# PCB.net
KiCad netlist of a schematic drawn in Altium Designer
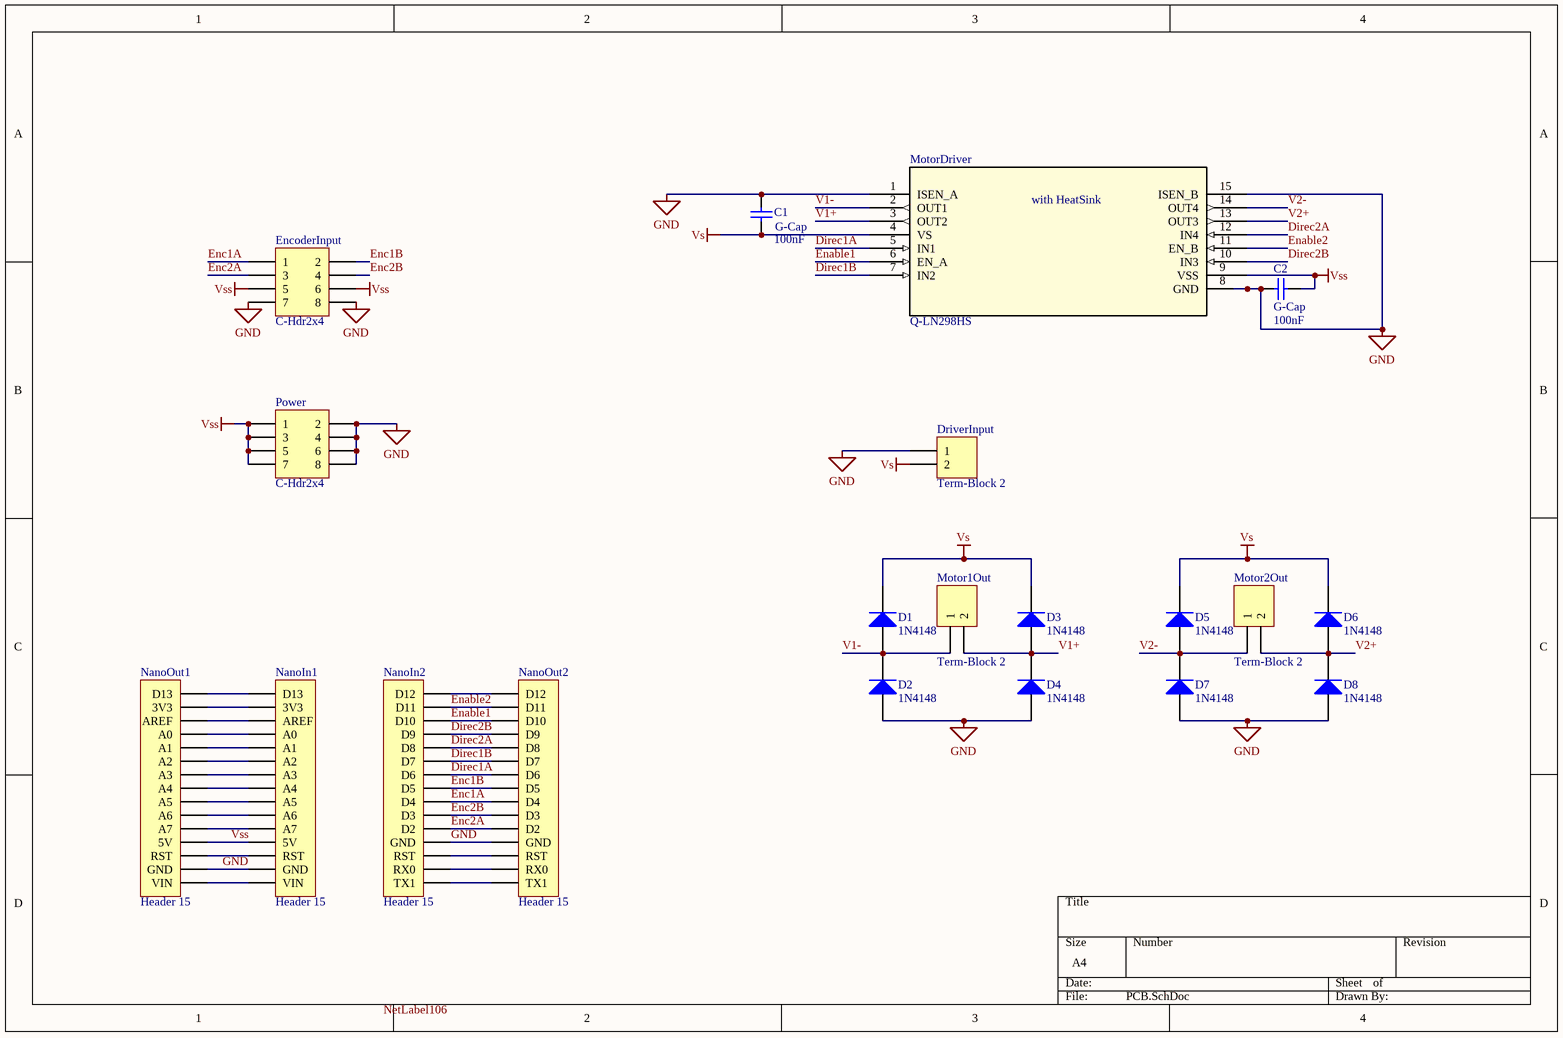
[diagram p0: PCB.SchDoc]

(export (version "E")
  (design (tool "Eeschema 10.0.6"))
  (components
    (comp (ref "C1")
      (value "G-Cap")
      (footprint "Cap2.54mm_LGE1.0")
      (description "Capacitor (specify value)")
      (fields (field (name "ALTIUM_VALUE") "100nF") (field (name "PUBLISHER") "Altium Limited"))
      (libsource (lib "PartsDatabaseV16.1") (part "G-Cap"))
    )
    (comp (ref "C2")
      (value "G-Cap")
      (footprint "Cap2.54mm_LGE1.0")
      (description "Capacitor (specify value)")
      (fields (field (name "ALTIUM_VALUE") "100nF") (field (name "PUBLISHER") "Altium Limited"))
      (libsource (lib "PartsDatabaseV16.1") (part "G-Cap"))
    )
    (comp (ref "D1")
      (value "1N4148")
      (footprint "DO-41_XLGE1.2")
      (description "High-speed Diode")
      (libsource (lib "PartsDatabaseV16.1") (part "T-DiodeRect"))
    )
    (comp (ref "D2")
      (value "1N4148")
      (footprint "DO-41_XLGE1.2")
      (description "High-speed Diode")
      (libsource (lib "PartsDatabaseV16.1") (part "T-DiodeRect"))
    )
    (comp (ref "D3")
      (value "1N4148")
      (footprint "DO-41_XLGE1.2")
      (description "High-speed Diode")
      (libsource (lib "PartsDatabaseV16.1") (part "T-DiodeRect"))
    )
    (comp (ref "D4")
      (value "1N4148")
      (footprint "DO-41_XLGE1.2")
      (description "High-speed Diode")
      (libsource (lib "PartsDatabaseV16.1") (part "T-DiodeRect"))
    )
    (comp (ref "D5")
      (value "1N4148")
      (footprint "DO-41_XLGE1.2")
      (description "High-speed Diode")
      (libsource (lib "PartsDatabaseV16.1") (part "T-DiodeRect"))
    )
    (comp (ref "D6")
      (value "1N4148")
      (footprint "DO-41_XLGE1.2")
      (description "High-speed Diode")
      (libsource (lib "PartsDatabaseV16.1") (part "T-DiodeRect"))
    )
    (comp (ref "D7")
      (value "1N4148")
      (footprint "DO-41_XLGE1.2")
      (description "High-speed Diode")
      (libsource (lib "PartsDatabaseV16.1") (part "T-DiodeRect"))
    )
    (comp (ref "D8")
      (value "1N4148")
      (footprint "DO-41_XLGE1.2")
      (description "High-speed Diode")
      (libsource (lib "PartsDatabaseV16.1") (part "T-DiodeRect"))
    )
    (comp (ref "DriverInput")
      (value "Term-Block 2")
      (footprint "TERM-BLOCK-5.08MM-2POS")
      (description "Terminal-Block 1x2")
      (fields (field (name "PUBLISHER") "Altium Limited"))
      (libsource (lib "PartsDatabaseV16.1") (part "C-Block2"))
    )
    (comp (ref "EncoderInput")
      (value "C-Hdr2x4")
      (footprint "HDR2X4_LGE1.0")
      (description "Header, 4-Pin, Dual row")
      (fields (field (name "PUBLISHER") "Altium Limited"))
      (libsource (lib "PartsDatabaseV16.1") (part "C-Hdr2x4"))
    )
    (comp (ref "Motor1Out")
      (value "Term-Block 2")
      (footprint "TERM-BLOCK-5.08MM-2POS")
      (description "Terminal-Block 1x2")
      (fields (field (name "PUBLISHER") "Altium Limited"))
      (libsource (lib "") (part "C-Block2_1"))
    )
    (comp (ref "Motor2Out")
      (value "Term-Block 2")
      (footprint "TERM-BLOCK-5.08MM-2POS")
      (description "Terminal-Block 1x2")
      (fields (field (name "PUBLISHER") "Altium Limited"))
      (libsource (lib "") (part "C-Block2_1"))
    )
    (comp (ref "MotorDriver")
      (value "Q-LN298HS")
      (footprint "Multiwatt15_V_ELEC391HS")
      (description "LN298 - IC Bridge Driver Par 15Multiwatt")
      (fields
        (field (name "MANUFACTURER_PART_NUMBER") "L298N")
        (field (name "COPYRIGHT") "Copyright (C) 2015 Accelerated Designs. All rights reserved")
      )
      (libsource (lib "Additional Parts 391") (part "Q-LN298HS"))
    )
    (comp (ref "NanoIn1")
      (value "Header 15")
      (footprint "HDR1X15")
      (description "Header, 15-Pin")
      (fields (field (name "PUBLISHER") "Altium Limited"))
      (libsource (lib "") (part "Header 15_2"))
    )
    (comp (ref "NanoIn2")
      (value "Header 15")
      (footprint "HDR1X15")
      (description "Header, 15-Pin")
      (fields (field (name "PUBLISHER") "Altium Limited"))
      (libsource (lib "Miscellaneous Connectors") (part "Header 15"))
    )
    (comp (ref "NanoOut1")
      (value "Header 15")
      (footprint "HDR1X15")
      (description "Header, 15-Pin")
      (fields (field (name "PUBLISHER") "Altium Limited"))
      (libsource (lib "Miscellaneous Connectors") (part "Header 15"))
    )
    (comp (ref "NanoOut2")
      (value "Header 15")
      (footprint "HDR1X15")
      (description "Header, 15-Pin")
      (fields (field (name "PUBLISHER") "Altium Limited"))
      (libsource (lib "") (part "Header 15_1"))
    )
    (comp (ref "Power")
      (value "C-Hdr2x4")
      (footprint "HDR2X4_LGE1.0")
      (description "Header, 4-Pin, Dual row")
      (fields (field (name "PUBLISHER") "Altium Limited"))
      (libsource (lib "PartsDatabaseV16.1") (part "C-Hdr2x4"))
    )
  )
  (nets
    (net (code "1") (name "/Direc1A") (class "Default")
      (node (ref "MotorDriver") (pin "5") (pinfunction "IN1_5") (pintype "input"))
      (node (ref "NanoIn2") (pin "7") (pinfunction "A3_7") (pintype "passive"))
      (node (ref "NanoOut2") (pin "7") (pinfunction "D6_7") (pintype "passive"))
    )
    (net (code "2") (name "/Direc1B") (class "Default")
      (node (ref "MotorDriver") (pin "7") (pinfunction "IN2_7") (pintype "input"))
      (node (ref "NanoIn2") (pin "6") (pinfunction "A2_6") (pintype "passive"))
      (node (ref "NanoOut2") (pin "6") (pinfunction "D7_6") (pintype "passive"))
    )
    (net (code "3") (name "/Direc2A") (class "Default")
      (node (ref "MotorDriver") (pin "12") (pinfunction "IN4_12") (pintype "input"))
      (node (ref "NanoIn2") (pin "5") (pinfunction "A1_5") (pintype "passive"))
      (node (ref "NanoOut2") (pin "5") (pinfunction "D8_5") (pintype "passive"))
    )
    (net (code "4") (name "/Direc2B") (class "Default")
      (node (ref "MotorDriver") (pin "10") (pinfunction "IN3_10") (pintype "input"))
      (node (ref "NanoIn2") (pin "4") (pinfunction "A0_4") (pintype "passive"))
      (node (ref "NanoOut2") (pin "4") (pinfunction "D9_4") (pintype "passive"))
    )
    (net (code "5") (name "/Enable1") (class "Default")
      (node (ref "MotorDriver") (pin "6") (pinfunction "EN_A_6") (pintype "input"))
      (node (ref "NanoIn2") (pin "3") (pinfunction "AREF_3") (pintype "passive"))
      (node (ref "NanoOut2") (pin "3") (pinfunction "D10_3") (pintype "passive"))
    )
    (net (code "6") (name "/Enable2") (class "Default")
      (node (ref "MotorDriver") (pin "11") (pinfunction "EN_B_11") (pintype "input"))
      (node (ref "NanoIn2") (pin "2") (pinfunction "3V3_2") (pintype "passive"))
      (node (ref "NanoOut2") (pin "2") (pinfunction "D11_2") (pintype "passive"))
    )
    (net (code "7") (name "/Enc1A") (class "Default")
      (node (ref "EncoderInput") (pin "1") (pinfunction "1_1") (pintype "passive"))
      (node (ref "NanoIn2") (pin "9") (pinfunction "A5_9") (pintype "passive"))
      (node (ref "NanoOut2") (pin "9") (pinfunction "D4_9") (pintype "passive"))
    )
    (net (code "8") (name "/Enc1B") (class "Default")
      (node (ref "EncoderInput") (pin "2") (pinfunction "2_2") (pintype "passive"))
      (node (ref "NanoIn2") (pin "8") (pinfunction "A4_8") (pintype "passive"))
      (node (ref "NanoOut2") (pin "8") (pinfunction "D5_8") (pintype "passive"))
    )
    (net (code "9") (name "/Enc2A") (class "Default")
      (node (ref "EncoderInput") (pin "3") (pinfunction "3_3") (pintype "passive"))
      (node (ref "NanoIn2") (pin "11") (pinfunction "A7_11") (pintype "passive"))
      (node (ref "NanoOut2") (pin "11") (pinfunction "D2_11") (pintype "passive"))
    )
    (net (code "10") (name "/Enc2B") (class "Default")
      (node (ref "EncoderInput") (pin "4") (pinfunction "4_4") (pintype "passive"))
      (node (ref "NanoIn2") (pin "10") (pinfunction "A6_10") (pintype "passive"))
      (node (ref "NanoOut2") (pin "10") (pinfunction "D3_10") (pintype "passive"))
    )
    (net (code "12") (name "/V1+") (class "Default")
      (node (ref "D3") (pin "1") (pinfunction "A_1") (pintype "passive"))
      (node (ref "D4") (pin "2") (pinfunction "K_2") (pintype "passive"))
      (node (ref "Motor1Out") (pin "2") (pinfunction "2_2") (pintype "passive"))
      (node (ref "MotorDriver") (pin "3") (pinfunction "OUT2_3") (pintype "output"))
    )
    (net (code "13") (name "/V1-") (class "Default")
      (node (ref "D1") (pin "1") (pinfunction "A_1") (pintype "passive"))
      (node (ref "D2") (pin "2") (pinfunction "K_2") (pintype "passive"))
      (node (ref "Motor1Out") (pin "1") (pinfunction "1_1") (pintype "passive"))
      (node (ref "MotorDriver") (pin "2") (pinfunction "OUT1_2") (pintype "output"))
    )
    (net (code "14") (name "/V2+") (class "Default")
      (node (ref "D6") (pin "1") (pinfunction "A_1") (pintype "passive"))
      (node (ref "D8") (pin "2") (pinfunction "K_2") (pintype "passive"))
      (node (ref "Motor2Out") (pin "2") (pinfunction "2_2") (pintype "passive"))
      (node (ref "MotorDriver") (pin "13") (pinfunction "OUT3_13") (pintype "output"))
    )
    (net (code "15") (name "/V2-") (class "Default")
      (node (ref "D5") (pin "1") (pinfunction "A_1") (pintype "passive"))
      (node (ref "D7") (pin "2") (pinfunction "K_2") (pintype "passive"))
      (node (ref "Motor2Out") (pin "1") (pinfunction "1_1") (pintype "passive"))
      (node (ref "MotorDriver") (pin "14") (pinfunction "OUT4_14") (pintype "output"))
    )
    (net (code "16") (name "GND") (class "Default")
      (node (ref "C1") (pin "2") (pinfunction "2_2") (pintype "passive"))
      (node (ref "C2") (pin "1") (pinfunction "1_1") (pintype "passive"))
      (node (ref "D2") (pin "1") (pinfunction "A_1") (pintype "passive"))
      (node (ref "D4") (pin "1") (pinfunction "A_1") (pintype "passive"))
      (node (ref "D7") (pin "1") (pinfunction "A_1") (pintype "passive"))
      (node (ref "D8") (pin "1") (pinfunction "A_1") (pintype "passive"))
      (node (ref "DriverInput") (pin "1") (pinfunction "1_1") (pintype "passive"))
      (node (ref "EncoderInput") (pin "7") (pinfunction "7_7") (pintype "passive"))
      (node (ref "EncoderInput") (pin "8") (pinfunction "8_8") (pintype "passive"))
      (node (ref "MotorDriver") (pin "1") (pinfunction "ISEN_A_1") (pintype "passive"))
      (node (ref "MotorDriver") (pin "15") (pinfunction "ISEN_B_15") (pintype "passive"))
      (node (ref "MotorDriver") (pin "8") (pinfunction "GND_8") (pintype "power_in"))
      (node (ref "NanoIn1") (pin "14") (pinfunction "GND_14") (pintype "passive"))
      (node (ref "NanoIn2") (pin "12") (pinfunction "5V_12") (pintype "passive"))
      (node (ref "NanoOut1") (pin "14") (pinfunction "GND_14") (pintype "passive"))
      (node (ref "NanoOut2") (pin "12") (pinfunction "GND_12") (pintype "passive"))
      (node (ref "Power") (pin "2") (pinfunction "2_2") (pintype "passive"))
      (node (ref "Power") (pin "4") (pinfunction "4_4") (pintype "passive"))
      (node (ref "Power") (pin "6") (pinfunction "6_6") (pintype "passive"))
      (node (ref "Power") (pin "8") (pinfunction "8_8") (pintype "passive"))
    )
    (net (code "17") (name "Net-(NanoIn1-3V3)") (class "Default")
      (node (ref "NanoIn1") (pin "2") (pinfunction "3V3_2") (pintype "passive"))
      (node (ref "NanoOut1") (pin "2") (pinfunction "3V3_2") (pintype "passive"))
    )
    (net (code "18") (name "Net-(NanoIn1-A0)") (class "Default")
      (node (ref "NanoIn1") (pin "4") (pinfunction "A0_4") (pintype "passive"))
      (node (ref "NanoOut1") (pin "4") (pinfunction "A0_4") (pintype "passive"))
    )
    (net (code "19") (name "Net-(NanoIn1-A1)") (class "Default")
      (node (ref "NanoIn1") (pin "5") (pinfunction "A1_5") (pintype "passive"))
      (node (ref "NanoOut1") (pin "5") (pinfunction "A1_5") (pintype "passive"))
    )
    (net (code "20") (name "Net-(NanoIn1-A2)") (class "Default")
      (node (ref "NanoIn1") (pin "6") (pinfunction "A2_6") (pintype "passive"))
      (node (ref "NanoOut1") (pin "6") (pinfunction "A2_6") (pintype "passive"))
    )
    (net (code "21") (name "Net-(NanoIn1-A3)") (class "Default")
      (node (ref "NanoIn1") (pin "7") (pinfunction "A3_7") (pintype "passive"))
      (node (ref "NanoOut1") (pin "7") (pinfunction "A3_7") (pintype "passive"))
    )
    (net (code "22") (name "Net-(NanoIn1-A4)") (class "Default")
      (node (ref "NanoIn1") (pin "8") (pinfunction "A4_8") (pintype "passive"))
      (node (ref "NanoOut1") (pin "8") (pinfunction "A4_8") (pintype "passive"))
    )
    (net (code "23") (name "Net-(NanoIn1-A5)") (class "Default")
      (node (ref "NanoIn1") (pin "9") (pinfunction "A5_9") (pintype "passive"))
      (node (ref "NanoOut1") (pin "9") (pinfunction "A5_9") (pintype "passive"))
    )
    (net (code "24") (name "Net-(NanoIn1-A6)") (class "Default")
      (node (ref "NanoIn1") (pin "10") (pinfunction "A6_10") (pintype "passive"))
      (node (ref "NanoOut1") (pin "10") (pinfunction "A6_10") (pintype "passive"))
    )
    (net (code "25") (name "Net-(NanoIn1-A7)") (class "Default")
      (node (ref "NanoIn1") (pin "11") (pinfunction "A7_11") (pintype "passive"))
      (node (ref "NanoOut1") (pin "11") (pinfunction "A7_11") (pintype "passive"))
    )
    (net (code "26") (name "Net-(NanoIn1-AREF)") (class "Default")
      (node (ref "NanoIn1") (pin "3") (pinfunction "AREF_3") (pintype "passive"))
      (node (ref "NanoOut1") (pin "3") (pinfunction "AREF_3") (pintype "passive"))
    )
    (net (code "27") (name "Net-(NanoIn1-D13)") (class "Default")
      (node (ref "NanoIn1") (pin "1") (pinfunction "D13_1") (pintype "passive"))
      (node (ref "NanoOut1") (pin "1") (pinfunction "D13_1") (pintype "passive"))
    )
    (net (code "28") (name "Net-(NanoIn1-RST)") (class "Default")
      (node (ref "NanoIn1") (pin "13") (pinfunction "RST_13") (pintype "passive"))
      (node (ref "NanoOut1") (pin "13") (pinfunction "RST_13") (pintype "passive"))
    )
    (net (code "29") (name "Net-(NanoIn1-VIN)") (class "Default")
      (node (ref "NanoIn1") (pin "15") (pinfunction "VIN_15") (pintype "passive"))
      (node (ref "NanoOut1") (pin "15") (pinfunction "VIN_15") (pintype "passive"))
    )
    (net (code "30") (name "Net-(NanoIn2-D13)") (class "Default")
      (node (ref "NanoIn2") (pin "1") (pinfunction "D13_1") (pintype "passive"))
      (node (ref "NanoOut2") (pin "1") (pinfunction "D12_1") (pintype "passive"))
    )
    (net (code "31") (name "Net-(NanoIn2-GND)") (class "Default")
      (node (ref "NanoIn2") (pin "14") (pinfunction "GND_14") (pintype "passive"))
      (node (ref "NanoOut2") (pin "14") (pinfunction "RX0_14") (pintype "passive"))
    )
    (net (code "32") (name "Net-(NanoIn2-RST)") (class "Default")
      (node (ref "NanoIn2") (pin "13") (pinfunction "RST_13") (pintype "passive"))
      (node (ref "NanoOut2") (pin "13") (pinfunction "RST_13") (pintype "passive"))
    )
    (net (code "33") (name "Net-(NanoIn2-VIN)") (class "Default")
      (node (ref "NanoIn2") (pin "15") (pinfunction "VIN_15") (pintype "passive"))
      (node (ref "NanoOut2") (pin "15") (pinfunction "TX1_15") (pintype "passive"))
    )
    (net (code "34") (name "Vs") (class "Default")
      (node (ref "C1") (pin "1") (pinfunction "1_1") (pintype "passive"))
      (node (ref "D1") (pin "2") (pinfunction "K_2") (pintype "passive"))
      (node (ref "D3") (pin "2") (pinfunction "K_2") (pintype "passive"))
      (node (ref "D5") (pin "2") (pinfunction "K_2") (pintype "passive"))
      (node (ref "D6") (pin "2") (pinfunction "K_2") (pintype "passive"))
      (node (ref "DriverInput") (pin "2") (pinfunction "2_2") (pintype "passive"))
      (node (ref "MotorDriver") (pin "4") (pinfunction "VS_4") (pintype "power_in"))
    )
    (net (code "35") (name "Vss") (class "Default")
      (node (ref "C2") (pin "2") (pinfunction "2_2") (pintype "passive"))
      (node (ref "EncoderInput") (pin "5") (pinfunction "5_5") (pintype "passive"))
      (node (ref "EncoderInput") (pin "6") (pinfunction "6_6") (pintype "passive"))
      (node (ref "MotorDriver") (pin "9") (pinfunction "VSS_9") (pintype "power_in"))
      (node (ref "NanoIn1") (pin "12") (pinfunction "5V_12") (pintype "passive"))
      (node (ref "NanoOut1") (pin "12") (pinfunction "5V_12") (pintype "passive"))
      (node (ref "Power") (pin "1") (pinfunction "1_1") (pintype "passive"))
      (node (ref "Power") (pin "3") (pinfunction "3_3") (pintype "passive"))
      (node (ref "Power") (pin "5") (pinfunction "5_5") (pintype "passive"))
      (node (ref "Power") (pin "7") (pinfunction "7_7") (pintype "passive"))
    )
  )
)
